# tiny_rack_v2_psu_exp_170.net
KiCad netlist of a schematic drawn in EAGLE
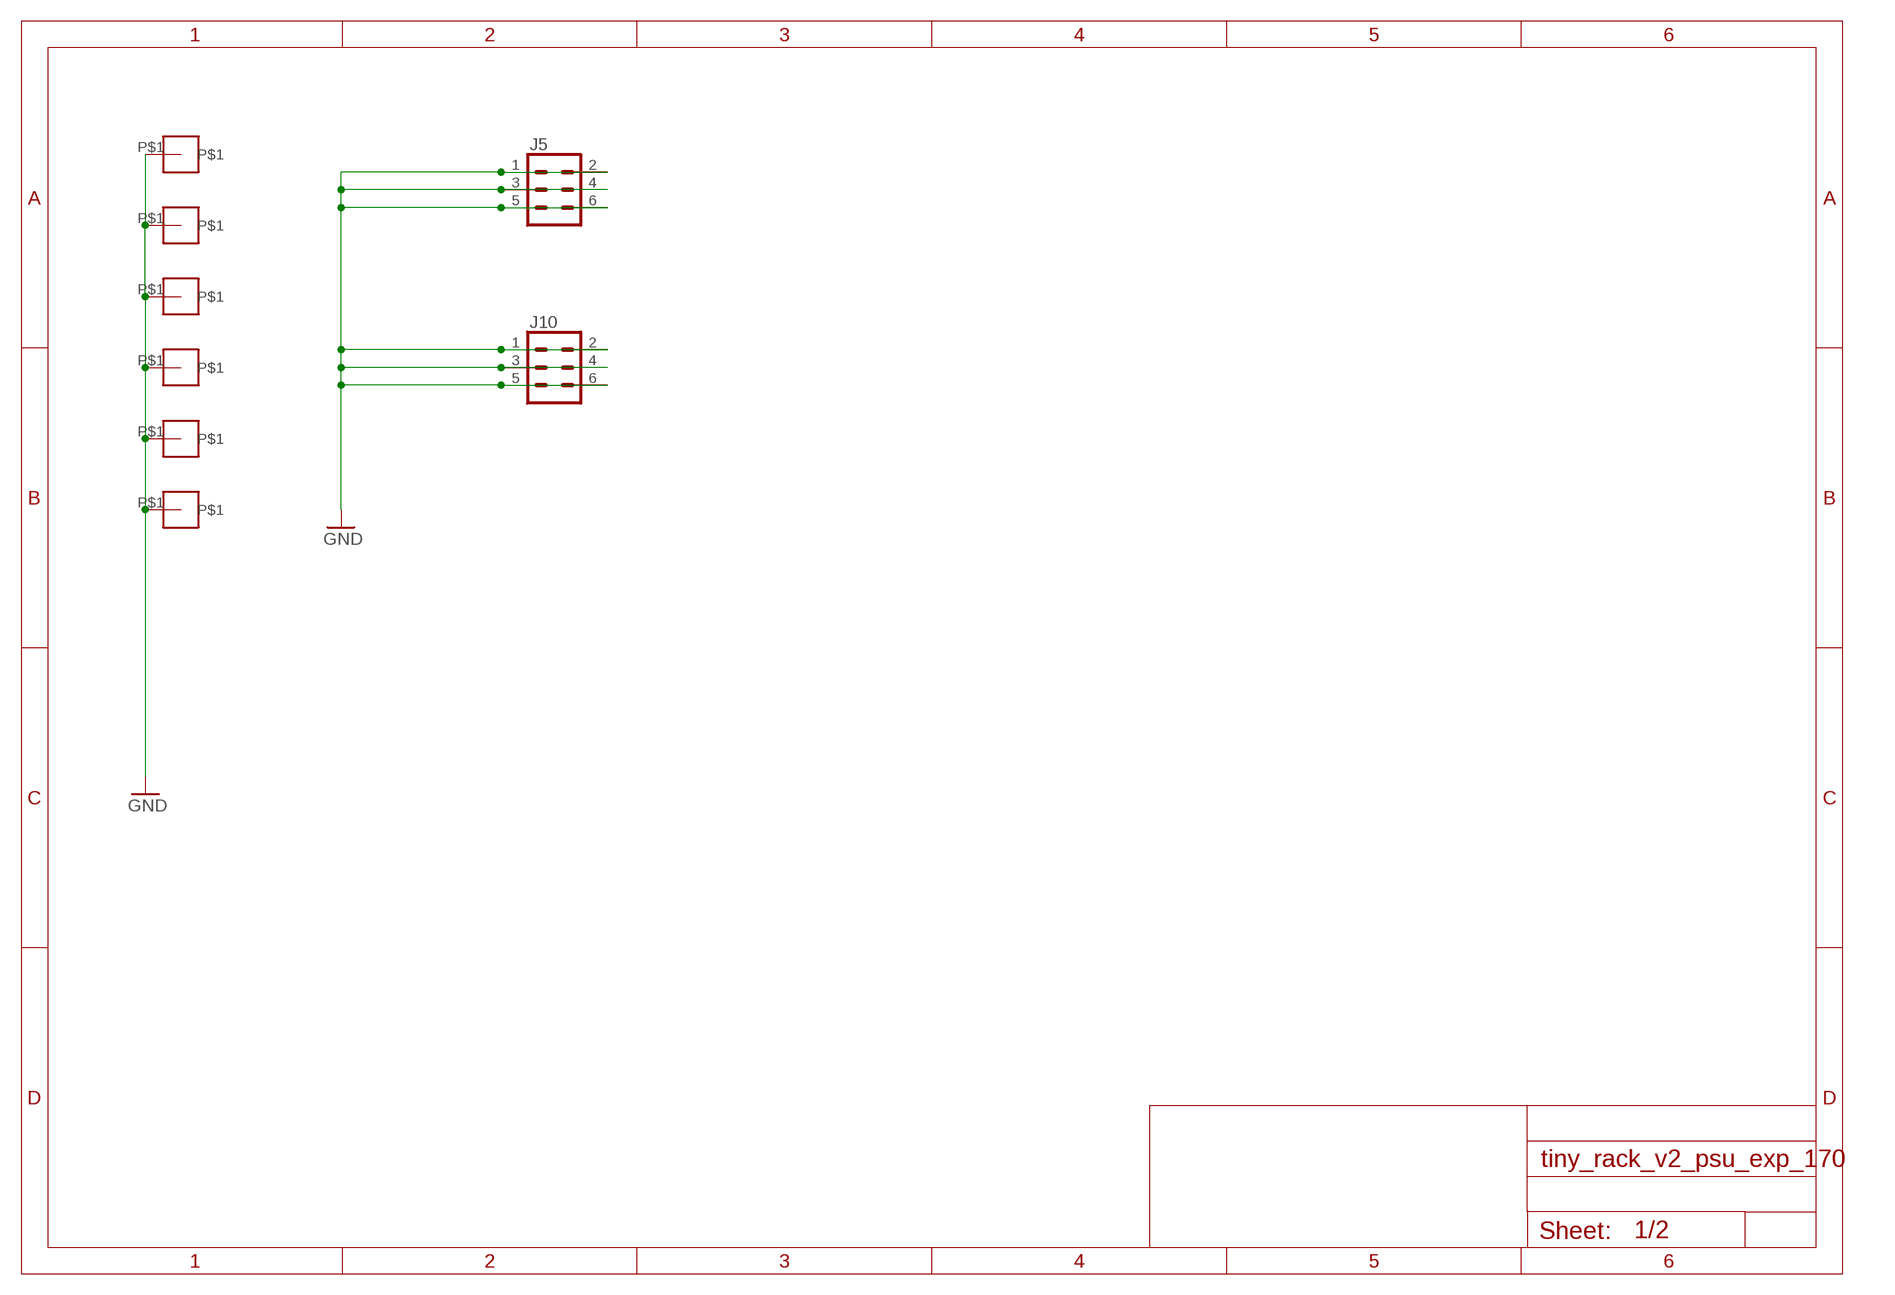
[diagram p0: schematic, sheet 1]
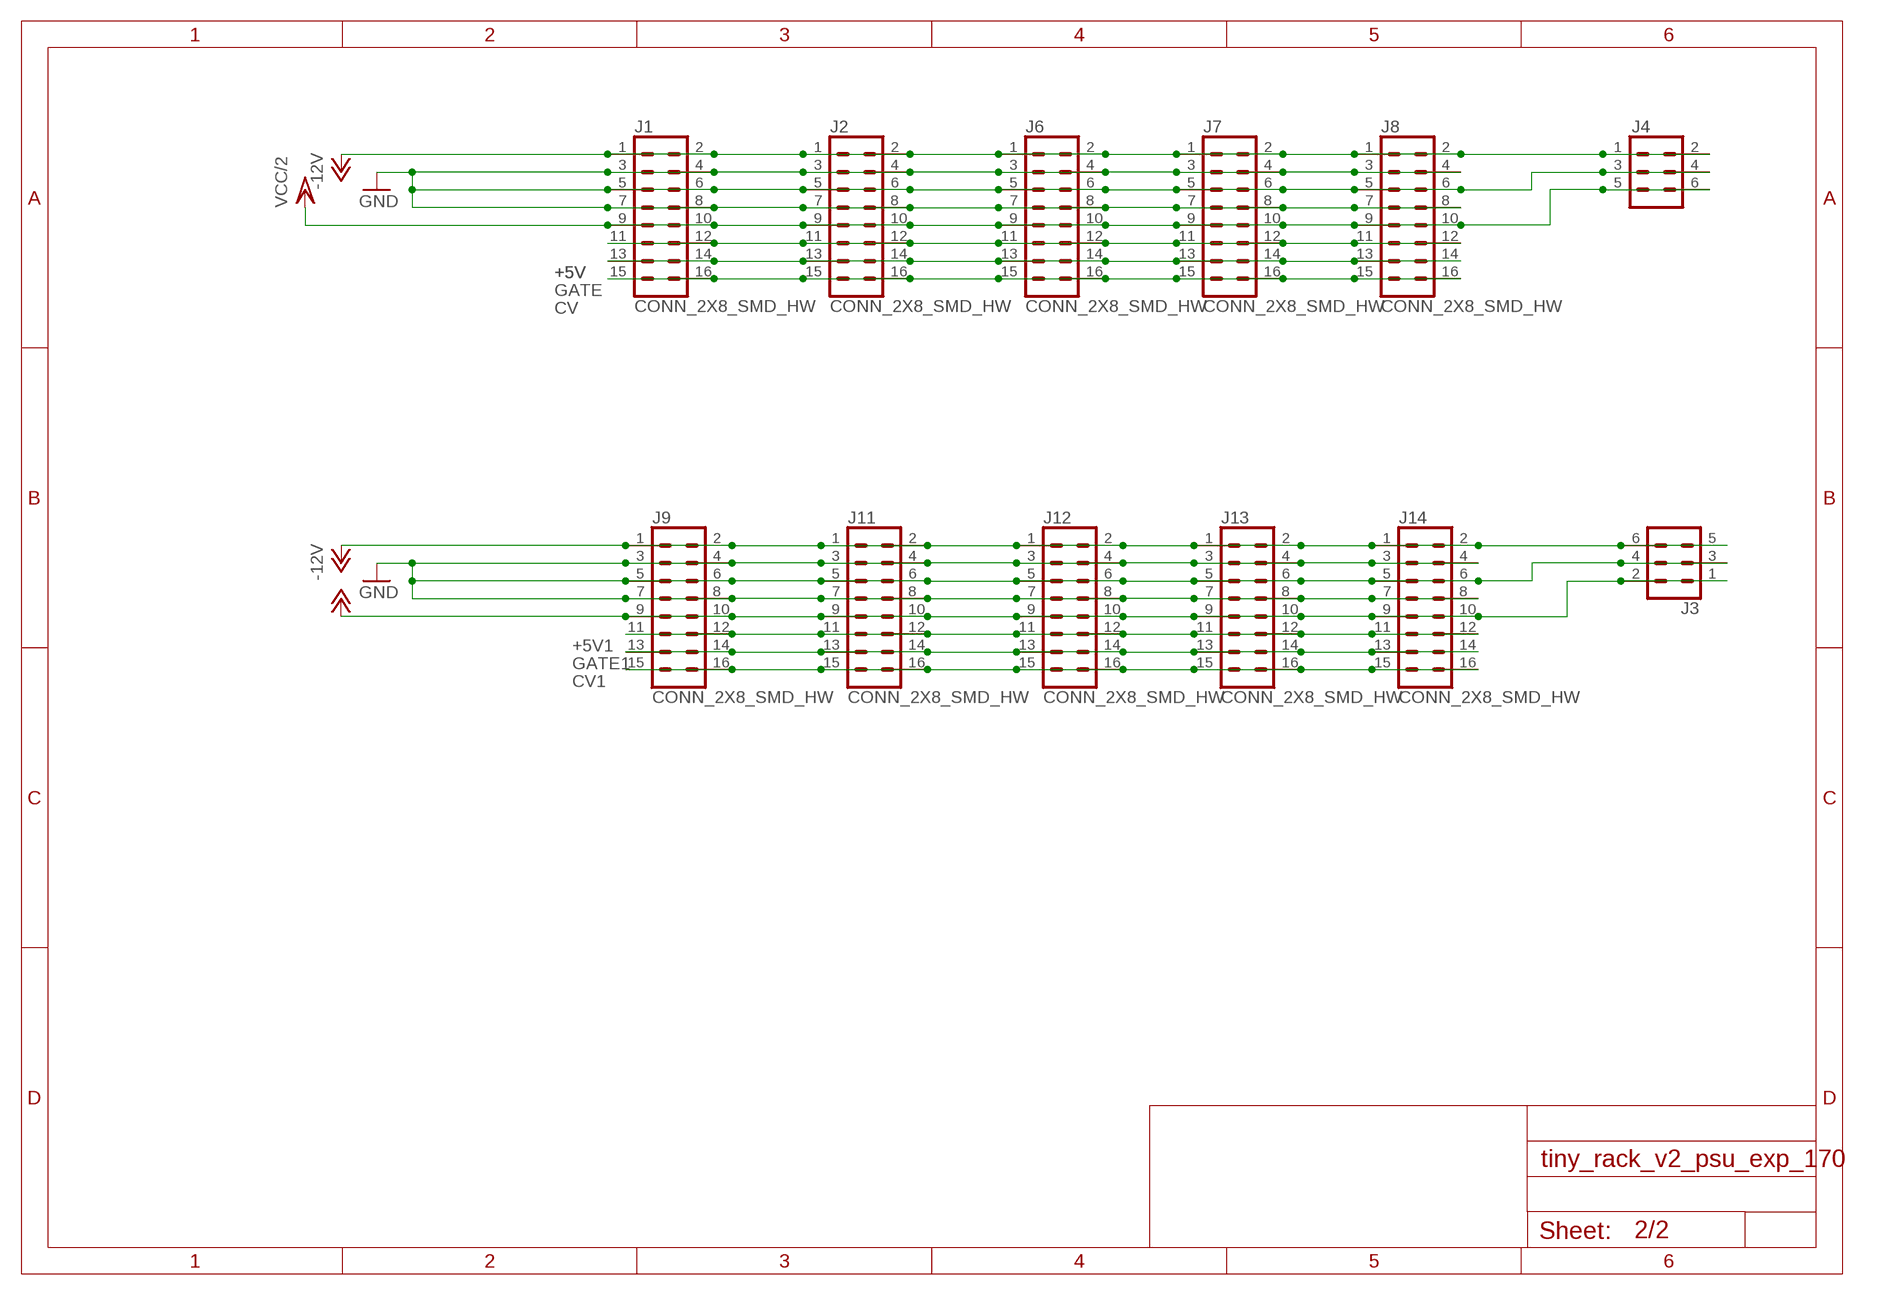
[diagram p1: schematic, sheet 2]

(export (version "E")
  (design (tool "Eeschema 10.0.6"))
  (components
    (comp (ref "J1")
      (value "CONN_2X8_SMD_HW")
      (footprint "eagle-import:2X8-SHROUDED_SMD_HW")
      (libsource (lib "eagle-import") (part "CONN_2X8_SMD_HW"))
    )
    (comp (ref "J2")
      (value "CONN_2X8_SMD_HW")
      (footprint "eagle-import:2X8-SHROUDED_SMD_HW")
      (libsource (lib "eagle-import") (part "CONN_2X8_SMD_HW"))
    )
    (comp (ref "J3")
      (value "CONN_03X2FEMALE_SMD")
      (footprint "eagle-import:2X3_SMD")
      (libsource (lib "eagle-import") (part "CONN_03X2FEMALE_SMD"))
    )
    (comp (ref "J4")
      (value "CONN_03X2FEMALE_SMD")
      (footprint "eagle-import:2X3_SMD")
      (libsource (lib "eagle-import") (part "CONN_03X2FEMALE_SMD"))
    )
    (comp (ref "J6")
      (value "CONN_2X8_SMD_HW")
      (footprint "eagle-import:2X8-SHROUDED_SMD_HW")
      (libsource (lib "eagle-import") (part "CONN_2X8_SMD_HW"))
    )
    (comp (ref "J7")
      (value "CONN_2X8_SMD_HW")
      (footprint "eagle-import:2X8-SHROUDED_SMD_HW")
      (libsource (lib "eagle-import") (part "CONN_2X8_SMD_HW"))
    )
    (comp (ref "J8")
      (value "CONN_2X8_SMD_HW")
      (footprint "eagle-import:2X8-SHROUDED_SMD_HW")
      (libsource (lib "eagle-import") (part "CONN_2X8_SMD_HW"))
    )
    (comp (ref "J9")
      (value "CONN_2X8_SMD_HW")
      (footprint "eagle-import:2X8-SHROUDED_SMD_HW")
      (libsource (lib "eagle-import") (part "CONN_2X8_SMD_HW"))
    )
    (comp (ref "J11")
      (value "CONN_2X8_SMD_HW")
      (footprint "eagle-import:2X8-SHROUDED_SMD_HW")
      (libsource (lib "eagle-import") (part "CONN_2X8_SMD_HW"))
    )
    (comp (ref "J12")
      (value "CONN_2X8_SMD_HW")
      (footprint "eagle-import:2X8-SHROUDED_SMD_HW")
      (libsource (lib "eagle-import") (part "CONN_2X8_SMD_HW"))
    )
    (comp (ref "J13")
      (value "CONN_2X8_SMD_HW")
      (footprint "eagle-import:2X8-SHROUDED_SMD_HW")
      (libsource (lib "eagle-import") (part "CONN_2X8_SMD_HW"))
    )
    (comp (ref "J14")
      (value "CONN_2X8_SMD_HW")
      (footprint "eagle-import:2X8-SHROUDED_SMD_HW")
      (libsource (lib "eagle-import") (part "CONN_2X8_SMD_HW"))
    )
    (comp (ref "J5")
      (value "CONN_03X2FEMALE_SMD")
      (footprint "eagle-import:2X3_SMD")
      (libsource (lib "eagle-import") (part "CONN_03X2FEMALE_SMD"))
    )
    (comp (ref "J10")
      (value "CONN_03X2FEMALE_SMD")
      (footprint "eagle-import:2X3_SMD")
      (libsource (lib "eagle-import") (part "CONN_03X2FEMALE_SMD"))
    )
    (comp (ref "U$1")
      (value "M3-HOLE")
      (footprint "eagle-import:M3-HOLE")
      (libsource (lib "eagle-import") (part "M3-HOLE"))
    )
    (comp (ref "U$2")
      (value "M3-HOLE")
      (footprint "eagle-import:M3-HOLE")
      (libsource (lib "eagle-import") (part "M3-HOLE"))
    )
    (comp (ref "U$3")
      (value "M3-HOLE")
      (footprint "eagle-import:M3-HOLE")
      (libsource (lib "eagle-import") (part "M3-HOLE"))
    )
    (comp (ref "U$4")
      (value "M3-HOLE")
      (footprint "eagle-import:M3-HOLE")
      (libsource (lib "eagle-import") (part "M3-HOLE"))
    )
    (comp (ref "U$5")
      (value "M3-HOLE")
      (footprint "eagle-import:M3-HOLE")
      (libsource (lib "eagle-import") (part "M3-HOLE"))
    )
    (comp (ref "U$6")
      (value "M3-HOLE")
      (footprint "eagle-import:M3-HOLE")
      (libsource (lib "eagle-import") (part "M3-HOLE"))
    )
  )
  (nets
    (net (code "1") (name "+5V") (class "Default")
      (node (ref "J1") (pin "11") (pinfunction "11_11") (pintype "passive"))
      (node (ref "J1") (pin "12") (pinfunction "12_12") (pintype "passive"))
      (node (ref "J2") (pin "11") (pinfunction "11_11") (pintype "passive"))
      (node (ref "J2") (pin "12") (pinfunction "12_12") (pintype "passive"))
      (node (ref "J6") (pin "11") (pinfunction "11_11") (pintype "passive"))
      (node (ref "J6") (pin "12") (pinfunction "12_12") (pintype "passive"))
      (node (ref "J7") (pin "11") (pinfunction "11_11") (pintype "passive"))
      (node (ref "J7") (pin "12") (pinfunction "12_12") (pintype "passive"))
      (node (ref "J8") (pin "11") (pinfunction "11_11") (pintype "passive"))
      (node (ref "J8") (pin "12") (pinfunction "12_12") (pintype "passive"))
    )
    (net (code "2") (name "+5V1") (class "Default")
      (node (ref "J11") (pin "11") (pinfunction "11_11") (pintype "passive"))
      (node (ref "J11") (pin "12") (pinfunction "12_12") (pintype "passive"))
      (node (ref "J12") (pin "11") (pinfunction "11_11") (pintype "passive"))
      (node (ref "J12") (pin "12") (pinfunction "12_12") (pintype "passive"))
      (node (ref "J13") (pin "11") (pinfunction "11_11") (pintype "passive"))
      (node (ref "J13") (pin "12") (pinfunction "12_12") (pintype "passive"))
      (node (ref "J14") (pin "11") (pinfunction "11_11") (pintype "passive"))
      (node (ref "J14") (pin "12") (pinfunction "12_12") (pintype "passive"))
      (node (ref "J9") (pin "11") (pinfunction "11_11") (pintype "passive"))
      (node (ref "J9") (pin "12") (pinfunction "12_12") (pintype "passive"))
    )
    (net (code "3") (name "+12V") (class "Default")
      (node (ref "J11") (pin "10") (pinfunction "10_10") (pintype "passive"))
      (node (ref "J11") (pin "9") (pinfunction "9_9") (pintype "passive"))
      (node (ref "J12") (pin "10") (pinfunction "10_10") (pintype "passive"))
      (node (ref "J12") (pin "9") (pinfunction "9_9") (pintype "passive"))
      (node (ref "J13") (pin "10") (pinfunction "10_10") (pintype "passive"))
      (node (ref "J13") (pin "9") (pinfunction "9_9") (pintype "passive"))
      (node (ref "J14") (pin "10") (pinfunction "10_10") (pintype "passive"))
      (node (ref "J14") (pin "9") (pinfunction "9_9") (pintype "passive"))
      (node (ref "J3") (pin "1") (pinfunction "1_1") (pintype "bidirectional"))
      (node (ref "J3") (pin "2") (pinfunction "2_2") (pintype "bidirectional"))
      (node (ref "J9") (pin "10") (pinfunction "10_10") (pintype "passive"))
      (node (ref "J9") (pin "9") (pinfunction "9_9") (pintype "passive"))
    )
    (net (code "4") (name "-12V") (class "Default")
      (node (ref "J1") (pin "1") (pinfunction "1_1") (pintype "passive"))
      (node (ref "J1") (pin "2") (pinfunction "2_2") (pintype "passive"))
      (node (ref "J11") (pin "1") (pinfunction "1_1") (pintype "passive"))
      (node (ref "J11") (pin "2") (pinfunction "2_2") (pintype "passive"))
      (node (ref "J12") (pin "1") (pinfunction "1_1") (pintype "passive"))
      (node (ref "J12") (pin "2") (pinfunction "2_2") (pintype "passive"))
      (node (ref "J13") (pin "1") (pinfunction "1_1") (pintype "passive"))
      (node (ref "J13") (pin "2") (pinfunction "2_2") (pintype "passive"))
      (node (ref "J14") (pin "1") (pinfunction "1_1") (pintype "passive"))
      (node (ref "J14") (pin "2") (pinfunction "2_2") (pintype "passive"))
      (node (ref "J2") (pin "1") (pinfunction "1_1") (pintype "passive"))
      (node (ref "J2") (pin "2") (pinfunction "2_2") (pintype "passive"))
      (node (ref "J3") (pin "5") (pinfunction "5_5") (pintype "bidirectional"))
      (node (ref "J3") (pin "6") (pinfunction "6_6") (pintype "bidirectional"))
      (node (ref "J4") (pin "1") (pinfunction "1_1") (pintype "bidirectional"))
      (node (ref "J4") (pin "2") (pinfunction "2_2") (pintype "bidirectional"))
      (node (ref "J6") (pin "1") (pinfunction "1_1") (pintype "passive"))
      (node (ref "J6") (pin "2") (pinfunction "2_2") (pintype "passive"))
      (node (ref "J7") (pin "1") (pinfunction "1_1") (pintype "passive"))
      (node (ref "J7") (pin "2") (pinfunction "2_2") (pintype "passive"))
      (node (ref "J8") (pin "1") (pinfunction "1_1") (pintype "passive"))
      (node (ref "J8") (pin "2") (pinfunction "2_2") (pintype "passive"))
      (node (ref "J9") (pin "1") (pinfunction "1_1") (pintype "passive"))
      (node (ref "J9") (pin "2") (pinfunction "2_2") (pintype "passive"))
    )
    (net (code "5") (name "CV") (class "Default")
      (node (ref "J1") (pin "15") (pinfunction "15_15") (pintype "passive"))
      (node (ref "J1") (pin "16") (pinfunction "16_16") (pintype "passive"))
      (node (ref "J2") (pin "15") (pinfunction "15_15") (pintype "passive"))
      (node (ref "J2") (pin "16") (pinfunction "16_16") (pintype "passive"))
      (node (ref "J6") (pin "15") (pinfunction "15_15") (pintype "passive"))
      (node (ref "J6") (pin "16") (pinfunction "16_16") (pintype "passive"))
      (node (ref "J7") (pin "15") (pinfunction "15_15") (pintype "passive"))
      (node (ref "J7") (pin "16") (pinfunction "16_16") (pintype "passive"))
      (node (ref "J8") (pin "15") (pinfunction "15_15") (pintype "passive"))
      (node (ref "J8") (pin "16") (pinfunction "16_16") (pintype "passive"))
    )
    (net (code "6") (name "CV1") (class "Default")
      (node (ref "J11") (pin "15") (pinfunction "15_15") (pintype "passive"))
      (node (ref "J11") (pin "16") (pinfunction "16_16") (pintype "passive"))
      (node (ref "J12") (pin "15") (pinfunction "15_15") (pintype "passive"))
      (node (ref "J12") (pin "16") (pinfunction "16_16") (pintype "passive"))
      (node (ref "J13") (pin "15") (pinfunction "15_15") (pintype "passive"))
      (node (ref "J13") (pin "16") (pinfunction "16_16") (pintype "passive"))
      (node (ref "J14") (pin "15") (pinfunction "15_15") (pintype "passive"))
      (node (ref "J14") (pin "16") (pinfunction "16_16") (pintype "passive"))
      (node (ref "J9") (pin "15") (pinfunction "15_15") (pintype "passive"))
      (node (ref "J9") (pin "16") (pinfunction "16_16") (pintype "passive"))
    )
    (net (code "7") (name "GATE") (class "Default")
      (node (ref "J1") (pin "13") (pinfunction "13_13") (pintype "passive"))
      (node (ref "J1") (pin "14") (pinfunction "14_14") (pintype "passive"))
      (node (ref "J2") (pin "13") (pinfunction "13_13") (pintype "passive"))
      (node (ref "J2") (pin "14") (pinfunction "14_14") (pintype "passive"))
      (node (ref "J6") (pin "13") (pinfunction "13_13") (pintype "passive"))
      (node (ref "J6") (pin "14") (pinfunction "14_14") (pintype "passive"))
      (node (ref "J7") (pin "13") (pinfunction "13_13") (pintype "passive"))
      (node (ref "J7") (pin "14") (pinfunction "14_14") (pintype "passive"))
      (node (ref "J8") (pin "13") (pinfunction "13_13") (pintype "passive"))
      (node (ref "J8") (pin "14") (pinfunction "14_14") (pintype "passive"))
    )
    (net (code "8") (name "GATE1") (class "Default")
      (node (ref "J11") (pin "13") (pinfunction "13_13") (pintype "passive"))
      (node (ref "J11") (pin "14") (pinfunction "14_14") (pintype "passive"))
      (node (ref "J12") (pin "13") (pinfunction "13_13") (pintype "passive"))
      (node (ref "J12") (pin "14") (pinfunction "14_14") (pintype "passive"))
      (node (ref "J13") (pin "13") (pinfunction "13_13") (pintype "passive"))
      (node (ref "J13") (pin "14") (pinfunction "14_14") (pintype "passive"))
      (node (ref "J14") (pin "13") (pinfunction "13_13") (pintype "passive"))
      (node (ref "J14") (pin "14") (pinfunction "14_14") (pintype "passive"))
      (node (ref "J9") (pin "13") (pinfunction "13_13") (pintype "passive"))
      (node (ref "J9") (pin "14") (pinfunction "14_14") (pintype "passive"))
    )
    (net (code "9") (name "GND") (class "Default")
      (node (ref "J1") (pin "3") (pinfunction "3_3") (pintype "passive"))
      (node (ref "J1") (pin "4") (pinfunction "4_4") (pintype "passive"))
      (node (ref "J1") (pin "5") (pinfunction "5_5") (pintype "passive"))
      (node (ref "J1") (pin "6") (pinfunction "6_6") (pintype "passive"))
      (node (ref "J1") (pin "7") (pinfunction "7_7") (pintype "passive"))
      (node (ref "J1") (pin "8") (pinfunction "8_8") (pintype "passive"))
      (node (ref "J10") (pin "1") (pinfunction "1_1") (pintype "bidirectional"))
      (node (ref "J10") (pin "2") (pinfunction "2_2") (pintype "bidirectional"))
      (node (ref "J10") (pin "3") (pinfunction "3_3") (pintype "bidirectional"))
      (node (ref "J10") (pin "4") (pinfunction "4_4") (pintype "bidirectional"))
      (node (ref "J10") (pin "5") (pinfunction "5_5") (pintype "bidirectional"))
      (node (ref "J10") (pin "6") (pinfunction "6_6") (pintype "bidirectional"))
      (node (ref "J11") (pin "3") (pinfunction "3_3") (pintype "passive"))
      (node (ref "J11") (pin "4") (pinfunction "4_4") (pintype "passive"))
      (node (ref "J11") (pin "5") (pinfunction "5_5") (pintype "passive"))
      (node (ref "J11") (pin "6") (pinfunction "6_6") (pintype "passive"))
      (node (ref "J11") (pin "7") (pinfunction "7_7") (pintype "passive"))
      (node (ref "J11") (pin "8") (pinfunction "8_8") (pintype "passive"))
      (node (ref "J12") (pin "3") (pinfunction "3_3") (pintype "passive"))
      (node (ref "J12") (pin "4") (pinfunction "4_4") (pintype "passive"))
      (node (ref "J12") (pin "5") (pinfunction "5_5") (pintype "passive"))
      (node (ref "J12") (pin "6") (pinfunction "6_6") (pintype "passive"))
      (node (ref "J12") (pin "7") (pinfunction "7_7") (pintype "passive"))
      (node (ref "J12") (pin "8") (pinfunction "8_8") (pintype "passive"))
      (node (ref "J13") (pin "3") (pinfunction "3_3") (pintype "passive"))
      (node (ref "J13") (pin "4") (pinfunction "4_4") (pintype "passive"))
      (node (ref "J13") (pin "5") (pinfunction "5_5") (pintype "passive"))
      (node (ref "J13") (pin "6") (pinfunction "6_6") (pintype "passive"))
      (node (ref "J13") (pin "7") (pinfunction "7_7") (pintype "passive"))
      (node (ref "J13") (pin "8") (pinfunction "8_8") (pintype "passive"))
      (node (ref "J14") (pin "3") (pinfunction "3_3") (pintype "passive"))
      (node (ref "J14") (pin "4") (pinfunction "4_4") (pintype "passive"))
      (node (ref "J14") (pin "5") (pinfunction "5_5") (pintype "passive"))
      (node (ref "J14") (pin "6") (pinfunction "6_6") (pintype "passive"))
      (node (ref "J14") (pin "7") (pinfunction "7_7") (pintype "passive"))
      (node (ref "J14") (pin "8") (pinfunction "8_8") (pintype "passive"))
      (node (ref "J2") (pin "3") (pinfunction "3_3") (pintype "passive"))
      (node (ref "J2") (pin "4") (pinfunction "4_4") (pintype "passive"))
      (node (ref "J2") (pin "5") (pinfunction "5_5") (pintype "passive"))
      (node (ref "J2") (pin "6") (pinfunction "6_6") (pintype "passive"))
      (node (ref "J2") (pin "7") (pinfunction "7_7") (pintype "passive"))
      (node (ref "J2") (pin "8") (pinfunction "8_8") (pintype "passive"))
      (node (ref "J3") (pin "3") (pinfunction "3_3") (pintype "bidirectional"))
      (node (ref "J3") (pin "4") (pinfunction "4_4") (pintype "bidirectional"))
      (node (ref "J4") (pin "3") (pinfunction "3_3") (pintype "bidirectional"))
      (node (ref "J4") (pin "4") (pinfunction "4_4") (pintype "bidirectional"))
      (node (ref "J5") (pin "1") (pinfunction "1_1") (pintype "bidirectional"))
      (node (ref "J5") (pin "2") (pinfunction "2_2") (pintype "bidirectional"))
      (node (ref "J5") (pin "3") (pinfunction "3_3") (pintype "bidirectional"))
      (node (ref "J5") (pin "4") (pinfunction "4_4") (pintype "bidirectional"))
      (node (ref "J5") (pin "5") (pinfunction "5_5") (pintype "bidirectional"))
      (node (ref "J5") (pin "6") (pinfunction "6_6") (pintype "bidirectional"))
      (node (ref "J6") (pin "3") (pinfunction "3_3") (pintype "passive"))
      (node (ref "J6") (pin "4") (pinfunction "4_4") (pintype "passive"))
      (node (ref "J6") (pin "5") (pinfunction "5_5") (pintype "passive"))
      (node (ref "J6") (pin "6") (pinfunction "6_6") (pintype "passive"))
      (node (ref "J6") (pin "7") (pinfunction "7_7") (pintype "passive"))
      (node (ref "J6") (pin "8") (pinfunction "8_8") (pintype "passive"))
      (node (ref "J7") (pin "3") (pinfunction "3_3") (pintype "passive"))
      (node (ref "J7") (pin "4") (pinfunction "4_4") (pintype "passive"))
      (node (ref "J7") (pin "5") (pinfunction "5_5") (pintype "passive"))
      (node (ref "J7") (pin "6") (pinfunction "6_6") (pintype "passive"))
      (node (ref "J7") (pin "7") (pinfunction "7_7") (pintype "passive"))
      (node (ref "J7") (pin "8") (pinfunction "8_8") (pintype "passive"))
      (node (ref "J8") (pin "3") (pinfunction "3_3") (pintype "passive"))
      (node (ref "J8") (pin "4") (pinfunction "4_4") (pintype "passive"))
      (node (ref "J8") (pin "5") (pinfunction "5_5") (pintype "passive"))
      (node (ref "J8") (pin "6") (pinfunction "6_6") (pintype "passive"))
      (node (ref "J8") (pin "7") (pinfunction "7_7") (pintype "passive"))
      (node (ref "J8") (pin "8") (pinfunction "8_8") (pintype "passive"))
      (node (ref "J9") (pin "3") (pinfunction "3_3") (pintype "passive"))
      (node (ref "J9") (pin "4") (pinfunction "4_4") (pintype "passive"))
      (node (ref "J9") (pin "5") (pinfunction "5_5") (pintype "passive"))
      (node (ref "J9") (pin "6") (pinfunction "6_6") (pintype "passive"))
      (node (ref "J9") (pin "7") (pinfunction "7_7") (pintype "passive"))
      (node (ref "J9") (pin "8") (pinfunction "8_8") (pintype "passive"))
      (node (ref "U$1") (pin "P$1") (pinfunction "P$1_P$1") (pintype "bidirectional"))
      (node (ref "U$2") (pin "P$1") (pinfunction "P$1_P$1") (pintype "bidirectional"))
      (node (ref "U$3") (pin "P$1") (pinfunction "P$1_P$1") (pintype "bidirectional"))
      (node (ref "U$4") (pin "P$1") (pinfunction "P$1_P$1") (pintype "bidirectional"))
      (node (ref "U$5") (pin "P$1") (pinfunction "P$1_P$1") (pintype "bidirectional"))
      (node (ref "U$6") (pin "P$1") (pinfunction "P$1_P$1") (pintype "bidirectional"))
    )
    (net (code "10") (name "VCC{slash}2") (class "Default")
      (node (ref "J1") (pin "10") (pinfunction "10_10") (pintype "passive"))
      (node (ref "J1") (pin "9") (pinfunction "9_9") (pintype "passive"))
      (node (ref "J2") (pin "10") (pinfunction "10_10") (pintype "passive"))
      (node (ref "J2") (pin "9") (pinfunction "9_9") (pintype "passive"))
      (node (ref "J4") (pin "5") (pinfunction "5_5") (pintype "bidirectional"))
      (node (ref "J4") (pin "6") (pinfunction "6_6") (pintype "bidirectional"))
      (node (ref "J6") (pin "10") (pinfunction "10_10") (pintype "passive"))
      (node (ref "J6") (pin "9") (pinfunction "9_9") (pintype "passive"))
      (node (ref "J7") (pin "10") (pinfunction "10_10") (pintype "passive"))
      (node (ref "J7") (pin "9") (pinfunction "9_9") (pintype "passive"))
      (node (ref "J8") (pin "10") (pinfunction "10_10") (pintype "passive"))
      (node (ref "J8") (pin "9") (pinfunction "9_9") (pintype "passive"))
    )
  )
)
